# leak.net
KiCad netlist of a schematic drawn in EAGLE
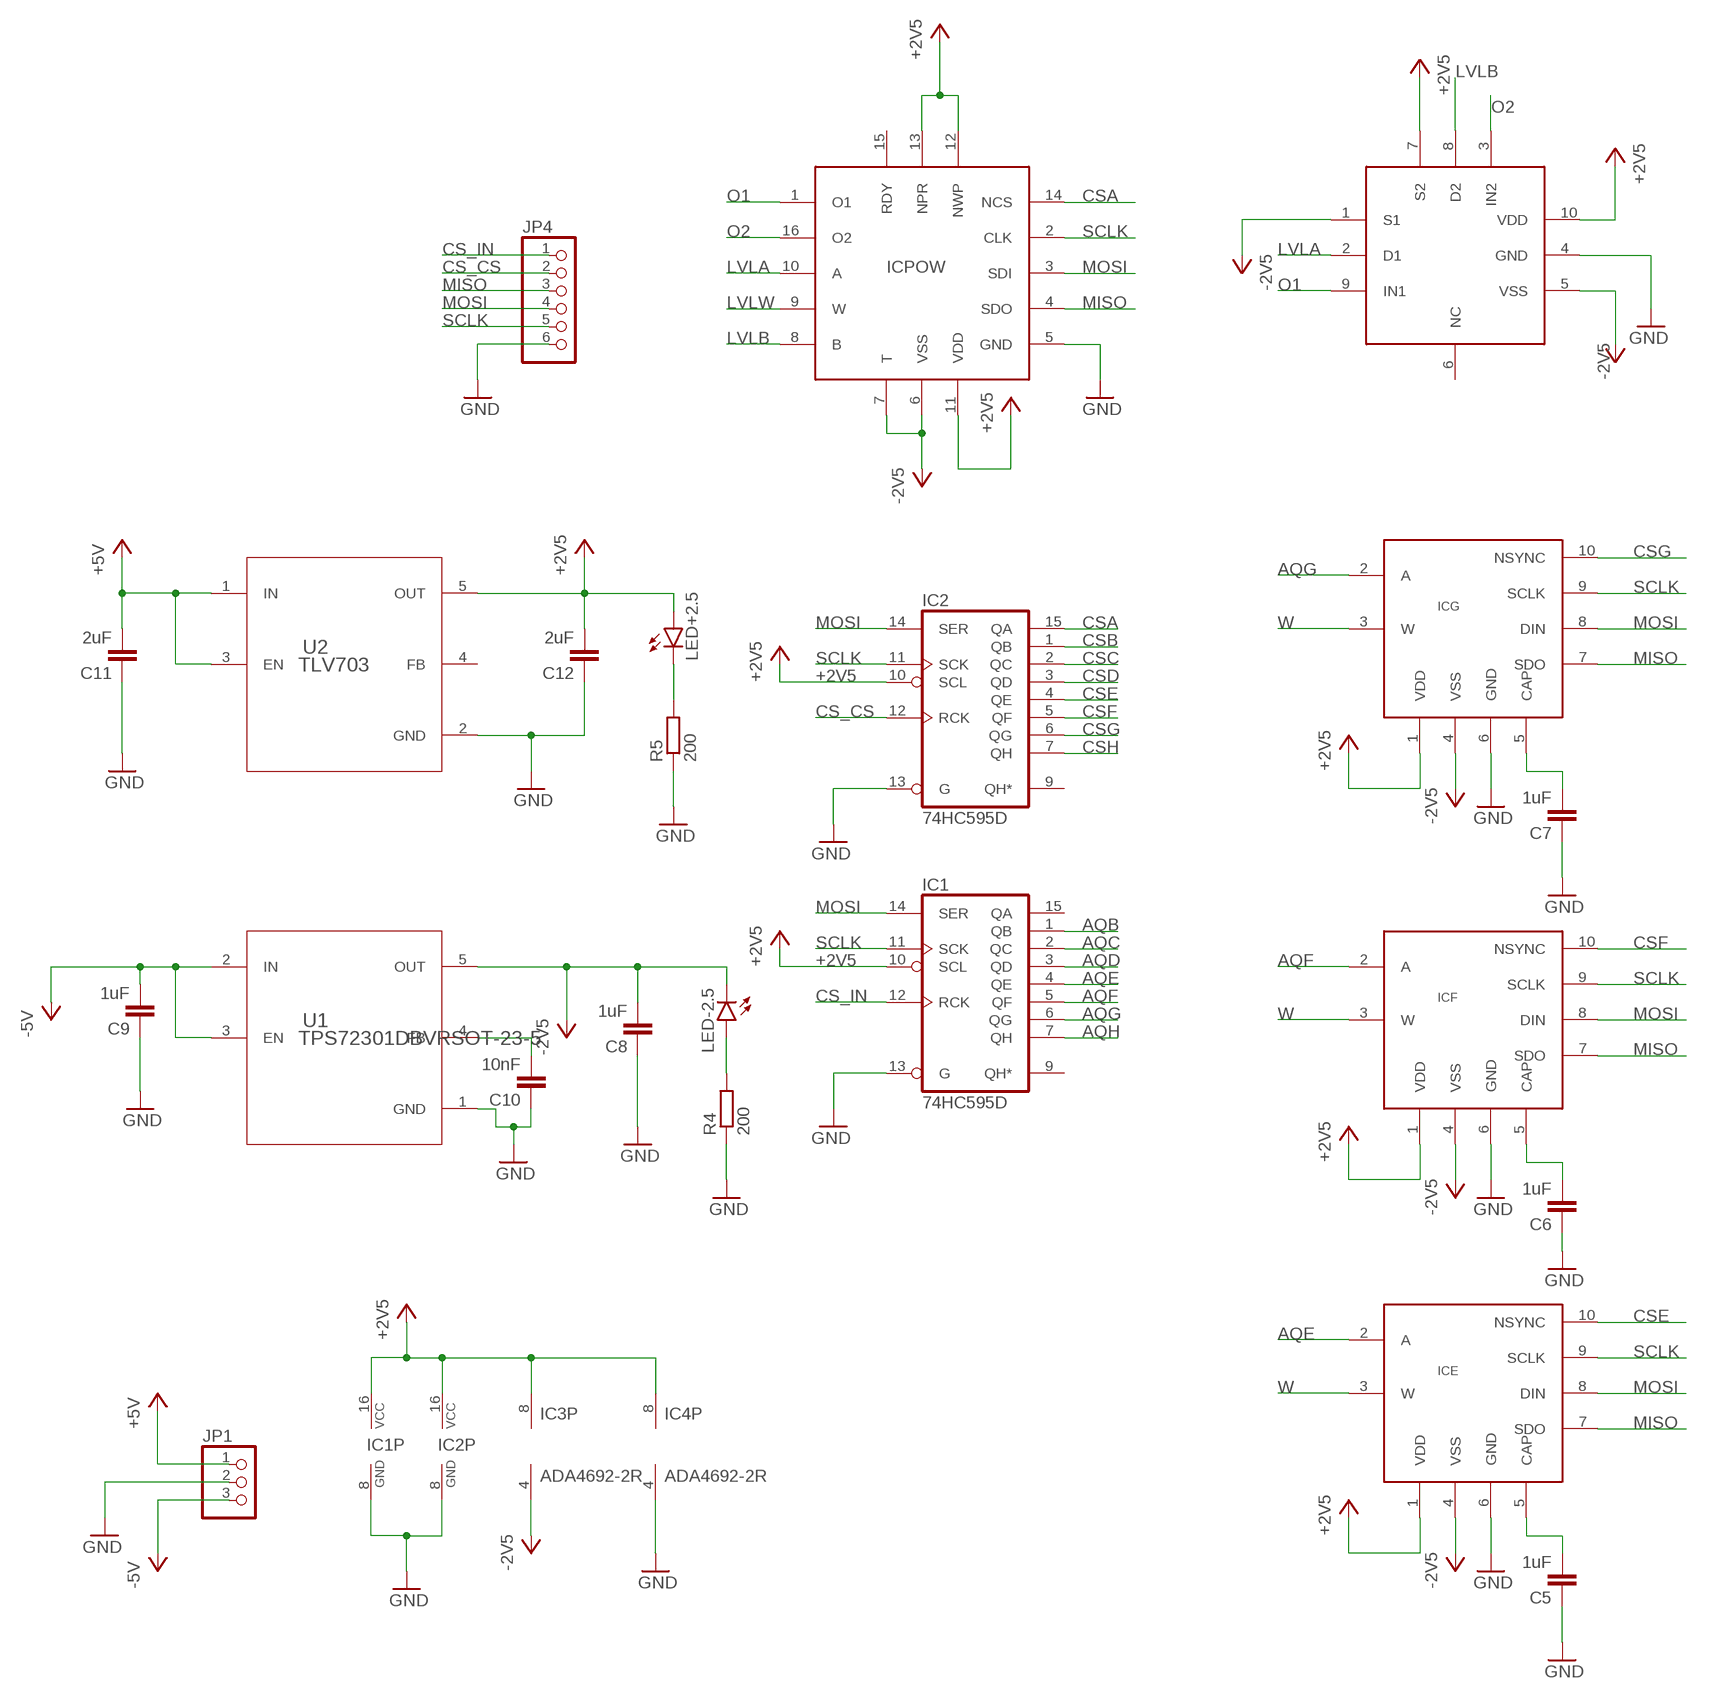
[diagram p0: schematic, sheet 1, part 1 of 2]
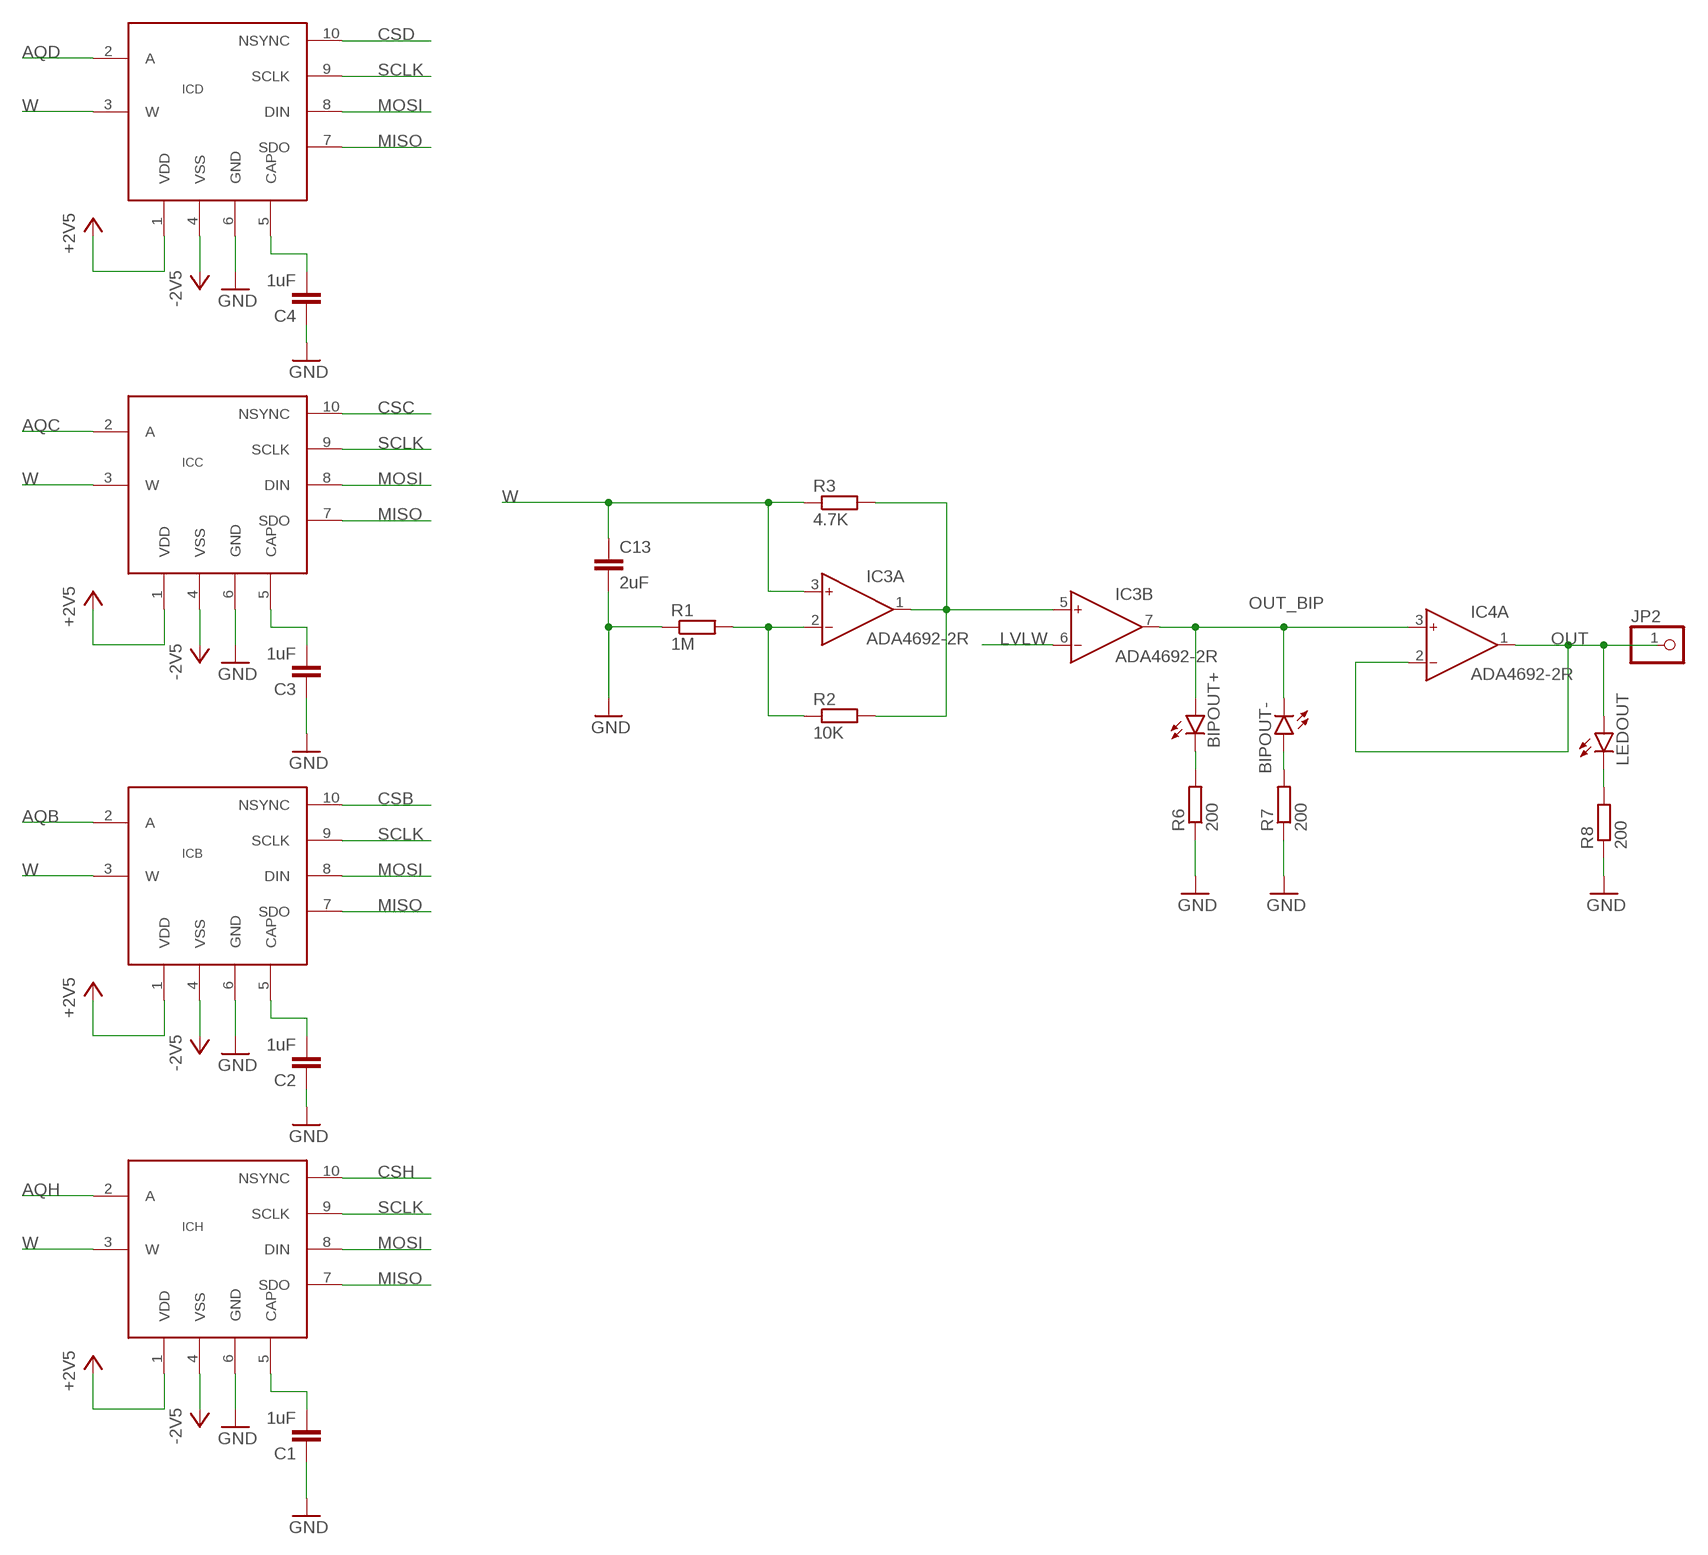
[diagram p1: schematic, sheet 1, part 2 of 2]

(export (version "E")
  (design (tool "Eeschema 10.0.6"))
  (components
    (comp (ref "BIPOUT+")
      (value "LEDCHIPLED_0805")
      (footprint "eagle-import:CHIPLED_0805")
      (libsource (lib "eagle-import") (part "LEDCHIPLED_0805"))
    )
    (comp (ref "BIPOUT-")
      (value "LEDCHIPLED_0805")
      (footprint "eagle-import:CHIPLED_0805")
      (libsource (lib "eagle-import") (part "LEDCHIPLED_0805"))
    )
    (comp (ref "C1")
      (value "1uF")
      (footprint "eagle-import:C0603")
      (libsource (lib "eagle-import") (part "C-EUC0603"))
    )
    (comp (ref "C2")
      (value "1uF")
      (footprint "eagle-import:C0603")
      (libsource (lib "eagle-import") (part "C-EUC0603"))
    )
    (comp (ref "C3")
      (value "1uF")
      (footprint "eagle-import:C0603")
      (libsource (lib "eagle-import") (part "C-EUC0603"))
    )
    (comp (ref "C4")
      (value "1uF")
      (footprint "eagle-import:C0603")
      (libsource (lib "eagle-import") (part "C-EUC0603"))
    )
    (comp (ref "C5")
      (value "1uF")
      (footprint "eagle-import:C0603")
      (libsource (lib "eagle-import") (part "C-EUC0603"))
    )
    (comp (ref "C6")
      (value "1uF")
      (footprint "eagle-import:C0603")
      (libsource (lib "eagle-import") (part "C-EUC0603"))
    )
    (comp (ref "C7")
      (value "1uF")
      (footprint "eagle-import:C0603")
      (libsource (lib "eagle-import") (part "C-EUC0603"))
    )
    (comp (ref "C8")
      (value "1uF")
      (footprint "eagle-import:C0603")
      (libsource (lib "eagle-import") (part "C-EUC0603"))
    )
    (comp (ref "C9")
      (value "1uF")
      (footprint "eagle-import:C0603")
      (libsource (lib "eagle-import") (part "C-EUC0603"))
    )
    (comp (ref "C10")
      (value "10nF")
      (footprint "eagle-import:C0603")
      (libsource (lib "eagle-import") (part "C-EUC0603"))
    )
    (comp (ref "C11")
      (value "2uF")
      (footprint "eagle-import:C0603")
      (libsource (lib "eagle-import") (part "C-EUC0603"))
    )
    (comp (ref "C12")
      (value "2uF")
      (footprint "eagle-import:C0603")
      (libsource (lib "eagle-import") (part "C-EUC0603"))
    )
    (comp (ref "C13")
      (value "2uF")
      (footprint "eagle-import:C0805K")
      (libsource (lib "eagle-import") (part "C-EUC0805K"))
    )
    (comp (ref "IC1")
      (value "74HC595D")
      (footprint "eagle-import:SO16")
      (libsource (lib "eagle-import") (part "74595DHC"))
    )
    (comp (ref "IC2")
      (value "74HC595D")
      (footprint "eagle-import:SO16")
      (libsource (lib "eagle-import") (part "74595DHC"))
    )
    (comp (ref "IC3")
      (value "ADA4692-2R")
      (footprint "eagle-import:SO8")
      (fields (field (name "MPN") "ADA4692-2ARZ"))
      (libsource (lib "eagle-import") (part "ADA4692-2R"))
    )
    (comp (ref "IC4")
      (value "ADA4692-2R")
      (footprint "eagle-import:SO8")
      (fields (field (name "MPN") "ADA4692-2ARZ"))
      (libsource (lib "eagle-import") (part "ADA4692-2R"))
    )
    (comp (ref "ICB")
      (value "AD5270MSOP10")
      (footprint "eagle-import:MSOP10")
      (libsource (lib "eagle-import") (part "AD5270MSOP10"))
    )
    (comp (ref "ICC")
      (value "AD5270MSOP10")
      (footprint "eagle-import:MSOP10")
      (libsource (lib "eagle-import") (part "AD5270MSOP10"))
    )
    (comp (ref "ICD")
      (value "AD5270MSOP10")
      (footprint "eagle-import:MSOP10")
      (libsource (lib "eagle-import") (part "AD5270MSOP10"))
    )
    (comp (ref "ICE")
      (value "AD5270MSOP10")
      (footprint "eagle-import:MSOP10")
      (libsource (lib "eagle-import") (part "AD5270MSOP10"))
    )
    (comp (ref "ICF")
      (value "AD5270MSOP10")
      (footprint "eagle-import:MSOP10")
      (libsource (lib "eagle-import") (part "AD5270MSOP10"))
    )
    (comp (ref "ICG")
      (value "AD5270MSOP10")
      (footprint "eagle-import:MSOP10")
      (libsource (lib "eagle-import") (part "AD5270MSOP10"))
    )
    (comp (ref "ICH")
      (value "AD5270MSOP10")
      (footprint "eagle-import:MSOP10")
      (libsource (lib "eagle-import") (part "AD5270MSOP10"))
    )
    (comp (ref "ICPOW")
      (value "AD5231")
      (footprint "eagle-import:TSSOP16")
      (libsource (lib "eagle-import") (part "AD5231"))
    )
    (comp (ref "ICSW")
      (value "ADG621")
      (footprint "eagle-import:MSOP10")
      (libsource (lib "eagle-import") (part "ADG621"))
    )
    (comp (ref "JP1")
      (value "PINHD-1X3")
      (footprint "eagle-import:1X03")
      (libsource (lib "eagle-import") (part "PINHD-1X3"))
    )
    (comp (ref "JP2")
      (value "PINHD-1X1")
      (footprint "eagle-import:1X01")
      (libsource (lib "eagle-import") (part "PINHD-1X1"))
    )
    (comp (ref "JP4")
      (value "PINHD-1X6")
      (footprint "eagle-import:1X06")
      (libsource (lib "eagle-import") (part "PINHD-1X6"))
    )
    (comp (ref "LED+2.5")
      (value "LEDCHIPLED_0805")
      (footprint "eagle-import:CHIPLED_0805")
      (libsource (lib "eagle-import") (part "LEDCHIPLED_0805"))
    )
    (comp (ref "LED-2.5")
      (value "LEDCHIPLED_0805")
      (footprint "eagle-import:CHIPLED_0805")
      (libsource (lib "eagle-import") (part "LEDCHIPLED_0805"))
    )
    (comp (ref "LEDOUT")
      (value "LEDCHIPLED_0805")
      (footprint "eagle-import:CHIPLED_0805")
      (libsource (lib "eagle-import") (part "LEDCHIPLED_0805"))
    )
    (comp (ref "R1")
      (value "1M")
      (footprint "eagle-import:R0805")
      (libsource (lib "eagle-import") (part "R-EU_R0805"))
    )
    (comp (ref "R2")
      (value "10K")
      (footprint "eagle-import:R0805")
      (libsource (lib "eagle-import") (part "R-EU_R0805"))
    )
    (comp (ref "R3")
      (value "4.7K")
      (footprint "eagle-import:R0805")
      (libsource (lib "eagle-import") (part "R-EU_R0805"))
    )
    (comp (ref "R4")
      (value "200")
      (footprint "eagle-import:R0603")
      (libsource (lib "eagle-import") (part "R-EU_R0603"))
    )
    (comp (ref "R5")
      (value "200")
      (footprint "eagle-import:R0603")
      (libsource (lib "eagle-import") (part "R-EU_R0603"))
    )
    (comp (ref "R6")
      (value "200")
      (footprint "eagle-import:R0603")
      (libsource (lib "eagle-import") (part "R-EU_R0603"))
    )
    (comp (ref "R7")
      (value "200")
      (footprint "eagle-import:R0603")
      (libsource (lib "eagle-import") (part "R-EU_R0603"))
    )
    (comp (ref "R8")
      (value "200")
      (footprint "eagle-import:R0603")
      (libsource (lib "eagle-import") (part "R-EU_R0603"))
    )
    (comp (ref "U1")
      (value "TPS72301DBVRSOT-23-5")
      (footprint "eagle-import:SOT95P280X145-5N")
      (libsource (lib "eagle-import") (part "TPS72301DBVRSOT-23-5"))
    )
    (comp (ref "U2")
      (value "TLV703")
      (footprint "eagle-import:SOT95P280X145-5N")
      (libsource (lib "eagle-import") (part "TLV703"))
    )
  )
  (nets
    (net (code "1") (name "+2V5") (class "Default")
      (node (ref "C12") (pin "2") (pinfunction "2_2") (pintype "passive"))
      (node (ref "IC1") (pin "10") (pinfunction "SCL_10") (pintype "input"))
      (node (ref "IC1") (pin "16") (pinfunction "VCC_16") (pintype "power_in"))
      (node (ref "IC2") (pin "10") (pinfunction "SCL_10") (pintype "input"))
      (node (ref "IC2") (pin "16") (pinfunction "VCC_16") (pintype "power_in"))
      (node (ref "IC3") (pin "8") (pinfunction "V+_8") (pintype "power_in"))
      (node (ref "IC4") (pin "8") (pinfunction "V+_8") (pintype "power_in"))
      (node (ref "ICB") (pin "1") (pinfunction "VDD_1") (pintype "bidirectional"))
      (node (ref "ICC") (pin "1") (pinfunction "VDD_1") (pintype "bidirectional"))
      (node (ref "ICD") (pin "1") (pinfunction "VDD_1") (pintype "bidirectional"))
      (node (ref "ICE") (pin "1") (pinfunction "VDD_1") (pintype "bidirectional"))
      (node (ref "ICF") (pin "1") (pinfunction "VDD_1") (pintype "bidirectional"))
      (node (ref "ICG") (pin "1") (pinfunction "VDD_1") (pintype "bidirectional"))
      (node (ref "ICH") (pin "1") (pinfunction "VDD_1") (pintype "bidirectional"))
      (node (ref "ICPOW") (pin "11") (pinfunction "VDD_11") (pintype "bidirectional"))
      (node (ref "ICPOW") (pin "12") (pinfunction "NWP_12") (pintype "bidirectional"))
      (node (ref "ICPOW") (pin "13") (pinfunction "NPR_13") (pintype "bidirectional"))
      (node (ref "ICSW") (pin "10") (pinfunction "VDD_10") (pintype "bidirectional"))
      (node (ref "ICSW") (pin "7") (pinfunction "S2_7") (pintype "bidirectional"))
      (node (ref "LED+2.5") (pin "A") (pinfunction "A_A") (pintype "passive"))
      (node (ref "U2") (pin "5") (pinfunction "OUT_5") (pintype "power_in"))
    )
    (net (code "2") (name "+5V") (class "Default")
      (node (ref "C11") (pin "2") (pinfunction "2_2") (pintype "passive"))
      (node (ref "JP1") (pin "1") (pinfunction "1_1") (pintype "passive"))
      (node (ref "U2") (pin "1") (pinfunction "IN_1") (pintype "power_in"))
      (node (ref "U2") (pin "3") (pinfunction "EN_3") (pintype "input"))
    )
    (net (code "3") (name "-2V5") (class "Default")
      (node (ref "C8") (pin "2") (pinfunction "2_2") (pintype "passive"))
      (node (ref "IC3") (pin "4") (pinfunction "V-_4") (pintype "power_in"))
      (node (ref "ICB") (pin "4") (pinfunction "VSS_4") (pintype "bidirectional"))
      (node (ref "ICC") (pin "4") (pinfunction "VSS_4") (pintype "bidirectional"))
      (node (ref "ICD") (pin "4") (pinfunction "VSS_4") (pintype "bidirectional"))
      (node (ref "ICE") (pin "4") (pinfunction "VSS_4") (pintype "bidirectional"))
      (node (ref "ICF") (pin "4") (pinfunction "VSS_4") (pintype "bidirectional"))
      (node (ref "ICG") (pin "4") (pinfunction "VSS_4") (pintype "bidirectional"))
      (node (ref "ICH") (pin "4") (pinfunction "VSS_4") (pintype "bidirectional"))
      (node (ref "ICPOW") (pin "6") (pinfunction "VSS_6") (pintype "bidirectional"))
      (node (ref "ICPOW") (pin "7") (pinfunction "T_7") (pintype "bidirectional"))
      (node (ref "ICSW") (pin "1") (pinfunction "S1_1") (pintype "bidirectional"))
      (node (ref "ICSW") (pin "5") (pinfunction "VSS_5") (pintype "bidirectional"))
      (node (ref "LED-2.5") (pin "C") (pinfunction "C_C") (pintype "passive"))
      (node (ref "U1") (pin "5") (pinfunction "OUT_5") (pintype "power_in"))
    )
    (net (code "4") (name "-5V") (class "Default")
      (node (ref "C9") (pin "2") (pinfunction "2_2") (pintype "passive"))
      (node (ref "JP1") (pin "3") (pinfunction "3_3") (pintype "passive"))
      (node (ref "U1") (pin "2") (pinfunction "IN_2") (pintype "power_in"))
      (node (ref "U1") (pin "3") (pinfunction "EN_3") (pintype "input"))
    )
    (net (code "5") (name "/AQB") (class "Default")
      (node (ref "IC1") (pin "1") (pinfunction "QB_1") (pintype "tri_state"))
      (node (ref "ICB") (pin "2") (pinfunction "A_2") (pintype "bidirectional"))
    )
    (net (code "6") (name "/AQC") (class "Default")
      (node (ref "IC1") (pin "2") (pinfunction "QC_2") (pintype "tri_state"))
      (node (ref "ICC") (pin "2") (pinfunction "A_2") (pintype "bidirectional"))
    )
    (net (code "7") (name "/AQD") (class "Default")
      (node (ref "IC1") (pin "3") (pinfunction "QD_3") (pintype "tri_state"))
      (node (ref "ICD") (pin "2") (pinfunction "A_2") (pintype "bidirectional"))
    )
    (net (code "8") (name "/AQE") (class "Default")
      (node (ref "IC1") (pin "4") (pinfunction "QE_4") (pintype "tri_state"))
      (node (ref "ICE") (pin "2") (pinfunction "A_2") (pintype "bidirectional"))
    )
    (net (code "9") (name "/AQF") (class "Default")
      (node (ref "IC1") (pin "5") (pinfunction "QF_5") (pintype "tri_state"))
      (node (ref "ICF") (pin "2") (pinfunction "A_2") (pintype "bidirectional"))
    )
    (net (code "10") (name "/AQG") (class "Default")
      (node (ref "IC1") (pin "6") (pinfunction "QG_6") (pintype "tri_state"))
      (node (ref "ICG") (pin "2") (pinfunction "A_2") (pintype "bidirectional"))
    )
    (net (code "11") (name "/AQH") (class "Default")
      (node (ref "IC1") (pin "7") (pinfunction "QH_7") (pintype "tri_state"))
      (node (ref "ICH") (pin "2") (pinfunction "A_2") (pintype "bidirectional"))
    )
    (net (code "12") (name "/CSA") (class "Default")
      (node (ref "IC2") (pin "15") (pinfunction "QA_15") (pintype "tri_state"))
      (node (ref "ICPOW") (pin "14") (pinfunction "NCS_14") (pintype "bidirectional"))
    )
    (net (code "13") (name "/CSB") (class "Default")
      (node (ref "IC2") (pin "1") (pinfunction "QB_1") (pintype "tri_state"))
      (node (ref "ICB") (pin "10") (pinfunction "NSYNC_10") (pintype "bidirectional"))
    )
    (net (code "14") (name "/CSC") (class "Default")
      (node (ref "IC2") (pin "2") (pinfunction "QC_2") (pintype "tri_state"))
      (node (ref "ICC") (pin "10") (pinfunction "NSYNC_10") (pintype "bidirectional"))
    )
    (net (code "15") (name "/CSD") (class "Default")
      (node (ref "IC2") (pin "3") (pinfunction "QD_3") (pintype "tri_state"))
      (node (ref "ICD") (pin "10") (pinfunction "NSYNC_10") (pintype "bidirectional"))
    )
    (net (code "16") (name "/CSE") (class "Default")
      (node (ref "IC2") (pin "4") (pinfunction "QE_4") (pintype "tri_state"))
      (node (ref "ICE") (pin "10") (pinfunction "NSYNC_10") (pintype "bidirectional"))
    )
    (net (code "17") (name "/CSF") (class "Default")
      (node (ref "IC2") (pin "5") (pinfunction "QF_5") (pintype "tri_state"))
      (node (ref "ICF") (pin "10") (pinfunction "NSYNC_10") (pintype "bidirectional"))
    )
    (net (code "18") (name "/CSG") (class "Default")
      (node (ref "IC2") (pin "6") (pinfunction "QG_6") (pintype "tri_state"))
      (node (ref "ICG") (pin "10") (pinfunction "NSYNC_10") (pintype "bidirectional"))
    )
    (net (code "19") (name "/CSH") (class "Default")
      (node (ref "IC2") (pin "7") (pinfunction "QH_7") (pintype "tri_state"))
      (node (ref "ICH") (pin "10") (pinfunction "NSYNC_10") (pintype "bidirectional"))
    )
    (net (code "20") (name "/CS_CS") (class "Default")
      (node (ref "IC2") (pin "12") (pinfunction "RCK_12") (pintype "input"))
      (node (ref "JP4") (pin "2") (pinfunction "2_2") (pintype "passive"))
    )
    (net (code "21") (name "/CS_IN") (class "Default")
      (node (ref "IC1") (pin "12") (pinfunction "RCK_12") (pintype "input"))
      (node (ref "JP4") (pin "1") (pinfunction "1_1") (pintype "passive"))
    )
    (net (code "22") (name "/LVLA") (class "Default")
      (node (ref "ICPOW") (pin "10") (pinfunction "A_10") (pintype "bidirectional"))
      (node (ref "ICSW") (pin "2") (pinfunction "D1_2") (pintype "bidirectional"))
    )
    (net (code "23") (name "/LVLB") (class "Default")
      (node (ref "ICPOW") (pin "8") (pinfunction "B_8") (pintype "bidirectional"))
      (node (ref "ICSW") (pin "8") (pinfunction "D2_8") (pintype "bidirectional"))
    )
    (net (code "24") (name "/LVLW") (class "Default")
      (node (ref "IC3") (pin "6") (pinfunction "IN-_6") (pintype "input"))
      (node (ref "ICPOW") (pin "9") (pinfunction "W_9") (pintype "bidirectional"))
    )
    (net (code "25") (name "/MISO") (class "Default")
      (node (ref "ICB") (pin "7") (pinfunction "SDO_7") (pintype "bidirectional"))
      (node (ref "ICC") (pin "7") (pinfunction "SDO_7") (pintype "bidirectional"))
      (node (ref "ICD") (pin "7") (pinfunction "SDO_7") (pintype "bidirectional"))
      (node (ref "ICE") (pin "7") (pinfunction "SDO_7") (pintype "bidirectional"))
      (node (ref "ICF") (pin "7") (pinfunction "SDO_7") (pintype "bidirectional"))
      (node (ref "ICG") (pin "7") (pinfunction "SDO_7") (pintype "bidirectional"))
      (node (ref "ICH") (pin "7") (pinfunction "SDO_7") (pintype "bidirectional"))
      (node (ref "ICPOW") (pin "4") (pinfunction "SDO_4") (pintype "bidirectional"))
      (node (ref "JP4") (pin "3") (pinfunction "3_3") (pintype "passive"))
    )
    (net (code "26") (name "/MOSI") (class "Default")
      (node (ref "IC1") (pin "14") (pinfunction "SER_14") (pintype "input"))
      (node (ref "IC2") (pin "14") (pinfunction "SER_14") (pintype "input"))
      (node (ref "ICB") (pin "8") (pinfunction "DIN_8") (pintype "bidirectional"))
      (node (ref "ICC") (pin "8") (pinfunction "DIN_8") (pintype "bidirectional"))
      (node (ref "ICD") (pin "8") (pinfunction "DIN_8") (pintype "bidirectional"))
      (node (ref "ICE") (pin "8") (pinfunction "DIN_8") (pintype "bidirectional"))
      (node (ref "ICF") (pin "8") (pinfunction "DIN_8") (pintype "bidirectional"))
      (node (ref "ICG") (pin "8") (pinfunction "DIN_8") (pintype "bidirectional"))
      (node (ref "ICH") (pin "8") (pinfunction "DIN_8") (pintype "bidirectional"))
      (node (ref "ICPOW") (pin "3") (pinfunction "SDI_3") (pintype "bidirectional"))
      (node (ref "JP4") (pin "4") (pinfunction "4_4") (pintype "passive"))
    )
    (net (code "27") (name "/O1") (class "Default")
      (node (ref "ICPOW") (pin "1") (pinfunction "O1_1") (pintype "bidirectional"))
      (node (ref "ICSW") (pin "9") (pinfunction "IN1_9") (pintype "bidirectional"))
    )
    (net (code "28") (name "/O2") (class "Default")
      (node (ref "ICPOW") (pin "16") (pinfunction "O2_16") (pintype "bidirectional"))
      (node (ref "ICSW") (pin "3") (pinfunction "IN2_3") (pintype "bidirectional"))
    )
    (net (code "29") (name "/OUT") (class "Default")
      (node (ref "IC4") (pin "1") (pinfunction "OUT_1") (pintype "output"))
      (node (ref "IC4") (pin "2") (pinfunction "IN-_2") (pintype "input"))
      (node (ref "JP2") (pin "1") (pinfunction "1_1") (pintype "passive"))
      (node (ref "LEDOUT") (pin "A") (pinfunction "A_A") (pintype "passive"))
    )
    (net (code "30") (name "/OUT_BIP") (class "Default")
      (node (ref "BIPOUT+") (pin "A") (pinfunction "A_A") (pintype "passive"))
      (node (ref "BIPOUT-") (pin "C") (pinfunction "C_C") (pintype "passive"))
      (node (ref "IC3") (pin "7") (pinfunction "OUT_7") (pintype "output"))
      (node (ref "IC4") (pin "3") (pinfunction "IN+_3") (pintype "input"))
    )
    (net (code "31") (name "/SCLK") (class "Default")
      (node (ref "IC1") (pin "11") (pinfunction "SCK_11") (pintype "input"))
      (node (ref "IC2") (pin "11") (pinfunction "SCK_11") (pintype "input"))
      (node (ref "ICB") (pin "9") (pinfunction "SCLK_9") (pintype "bidirectional"))
      (node (ref "ICC") (pin "9") (pinfunction "SCLK_9") (pintype "bidirectional"))
      (node (ref "ICD") (pin "9") (pinfunction "SCLK_9") (pintype "bidirectional"))
      (node (ref "ICE") (pin "9") (pinfunction "SCLK_9") (pintype "bidirectional"))
      (node (ref "ICF") (pin "9") (pinfunction "SCLK_9") (pintype "bidirectional"))
      (node (ref "ICG") (pin "9") (pinfunction "SCLK_9") (pintype "bidirectional"))
      (node (ref "ICH") (pin "9") (pinfunction "SCLK_9") (pintype "bidirectional"))
      (node (ref "ICPOW") (pin "2") (pinfunction "CLK_2") (pintype "bidirectional"))
      (node (ref "JP4") (pin "5") (pinfunction "5_5") (pintype "passive"))
    )
    (net (code "32") (name "/W") (class "Default")
      (node (ref "C13") (pin "1") (pinfunction "1_1") (pintype "passive"))
      (node (ref "IC3") (pin "3") (pinfunction "IN+_3") (pintype "input"))
      (node (ref "ICB") (pin "3") (pinfunction "W_3") (pintype "bidirectional"))
      (node (ref "ICC") (pin "3") (pinfunction "W_3") (pintype "bidirectional"))
      (node (ref "ICD") (pin "3") (pinfunction "W_3") (pintype "bidirectional"))
      (node (ref "ICE") (pin "3") (pinfunction "W_3") (pintype "bidirectional"))
      (node (ref "ICF") (pin "3") (pinfunction "W_3") (pintype "bidirectional"))
      (node (ref "ICG") (pin "3") (pinfunction "W_3") (pintype "bidirectional"))
      (node (ref "ICH") (pin "3") (pinfunction "W_3") (pintype "bidirectional"))
      (node (ref "R3") (pin "1") (pinfunction "1_1") (pintype "passive"))
    )
    (net (code "33") (name "GND") (class "Default")
      (node (ref "C1") (pin "1") (pinfunction "1_1") (pintype "passive"))
      (node (ref "C10") (pin "1") (pinfunction "1_1") (pintype "passive"))
      (node (ref "C11") (pin "1") (pinfunction "1_1") (pintype "passive"))
      (node (ref "C12") (pin "1") (pinfunction "1_1") (pintype "passive"))
      (node (ref "C13") (pin "2") (pinfunction "2_2") (pintype "passive"))
      (node (ref "C2") (pin "1") (pinfunction "1_1") (pintype "passive"))
      (node (ref "C3") (pin "1") (pinfunction "1_1") (pintype "passive"))
      (node (ref "C4") (pin "1") (pinfunction "1_1") (pintype "passive"))
      (node (ref "C5") (pin "1") (pinfunction "1_1") (pintype "passive"))
      (node (ref "C6") (pin "1") (pinfunction "1_1") (pintype "passive"))
      (node (ref "C7") (pin "1") (pinfunction "1_1") (pintype "passive"))
      (node (ref "C8") (pin "1") (pinfunction "1_1") (pintype "passive"))
      (node (ref "C9") (pin "1") (pinfunction "1_1") (pintype "passive"))
      (node (ref "IC1") (pin "13") (pinfunction "G_13") (pintype "input"))
      (node (ref "IC1") (pin "8") (pinfunction "GND_8") (pintype "power_in"))
      (node (ref "IC2") (pin "13") (pinfunction "G_13") (pintype "input"))
      (node (ref "IC2") (pin "8") (pinfunction "GND_8") (pintype "power_in"))
      (node (ref "IC4") (pin "4") (pinfunction "V-_4") (pintype "power_in"))
      (node (ref "ICB") (pin "6") (pinfunction "GND_6") (pintype "bidirectional"))
      (node (ref "ICC") (pin "6") (pinfunction "GND_6") (pintype "bidirectional"))
      (node (ref "ICD") (pin "6") (pinfunction "GND_6") (pintype "bidirectional"))
      (node (ref "ICE") (pin "6") (pinfunction "GND_6") (pintype "bidirectional"))
      (node (ref "ICF") (pin "6") (pinfunction "GND_6") (pintype "bidirectional"))
      (node (ref "ICG") (pin "6") (pinfunction "GND_6") (pintype "bidirectional"))
      (node (ref "ICH") (pin "6") (pinfunction "GND_6") (pintype "bidirectional"))
      (node (ref "ICPOW") (pin "5") (pinfunction "GND_5") (pintype "bidirectional"))
      (node (ref "ICSW") (pin "4") (pinfunction "GND_4") (pintype "bidirectional"))
      (node (ref "JP1") (pin "2") (pinfunction "2_2") (pintype "passive"))
      (node (ref "JP4") (pin "6") (pinfunction "6_6") (pintype "passive"))
      (node (ref "R1") (pin "1") (pinfunction "1_1") (pintype "passive"))
      (node (ref "R4") (pin "1") (pinfunction "1_1") (pintype "passive"))
      (node (ref "R5") (pin "1") (pinfunction "1_1") (pintype "passive"))
      (node (ref "R6") (pin "1") (pinfunction "1_1") (pintype "passive"))
      (node (ref "R7") (pin "1") (pinfunction "1_1") (pintype "passive"))
      (node (ref "R8") (pin "1") (pinfunction "1_1") (pintype "passive"))
      (node (ref "U1") (pin "1") (pinfunction "GND_1") (pintype "power_in"))
      (node (ref "U2") (pin "2") (pinfunction "GND_2") (pintype "power_in"))
    )
    (net (code "34") (name "Net-(BIPOUT+-PadC)") (class "Default")
      (node (ref "BIPOUT+") (pin "C") (pinfunction "C_C") (pintype "passive"))
      (node (ref "R6") (pin "2") (pinfunction "2_2") (pintype "passive"))
    )
    (net (code "35") (name "Net-(BIPOUT--PadA)") (class "Default")
      (node (ref "BIPOUT-") (pin "A") (pinfunction "A_A") (pintype "passive"))
      (node (ref "R7") (pin "2") (pinfunction "2_2") (pintype "passive"))
    )
    (net (code "36") (name "Net-(IC3A-IN-)") (class "Default")
      (node (ref "IC3") (pin "2") (pinfunction "IN-_2") (pintype "input"))
      (node (ref "R1") (pin "2") (pinfunction "2_2") (pintype "passive"))
      (node (ref "R2") (pin "1") (pinfunction "1_1") (pintype "passive"))
    )
    (net (code "37") (name "Net-(IC3A-OUT)") (class "Default")
      (node (ref "IC3") (pin "1") (pinfunction "OUT_1") (pintype "output"))
      (node (ref "IC3") (pin "5") (pinfunction "IN+_5") (pintype "input"))
      (node (ref "R2") (pin "2") (pinfunction "2_2") (pintype "passive"))
      (node (ref "R3") (pin "2") (pinfunction "2_2") (pintype "passive"))
    )
    (net (code "38") (name "Net-(ICB-CAP)") (class "Default")
      (node (ref "C2") (pin "2") (pinfunction "2_2") (pintype "passive"))
      (node (ref "ICB") (pin "5") (pinfunction "CAP_5") (pintype "bidirectional"))
    )
    (net (code "39") (name "Net-(ICC-CAP)") (class "Default")
      (node (ref "C3") (pin "2") (pinfunction "2_2") (pintype "passive"))
      (node (ref "ICC") (pin "5") (pinfunction "CAP_5") (pintype "bidirectional"))
    )
    (net (code "40") (name "Net-(ICD-CAP)") (class "Default")
      (node (ref "C4") (pin "2") (pinfunction "2_2") (pintype "passive"))
      (node (ref "ICD") (pin "5") (pinfunction "CAP_5") (pintype "bidirectional"))
    )
    (net (code "41") (name "Net-(ICE-CAP)") (class "Default")
      (node (ref "C5") (pin "2") (pinfunction "2_2") (pintype "passive"))
      (node (ref "ICE") (pin "5") (pinfunction "CAP_5") (pintype "bidirectional"))
    )
    (net (code "42") (name "Net-(ICF-CAP)") (class "Default")
      (node (ref "C6") (pin "2") (pinfunction "2_2") (pintype "passive"))
      (node (ref "ICF") (pin "5") (pinfunction "CAP_5") (pintype "bidirectional"))
    )
    (net (code "43") (name "Net-(ICG-CAP)") (class "Default")
      (node (ref "C7") (pin "2") (pinfunction "2_2") (pintype "passive"))
      (node (ref "ICG") (pin "5") (pinfunction "CAP_5") (pintype "bidirectional"))
    )
    (net (code "44") (name "Net-(ICH-CAP)") (class "Default")
      (node (ref "C1") (pin "2") (pinfunction "2_2") (pintype "passive"))
      (node (ref "ICH") (pin "5") (pinfunction "CAP_5") (pintype "bidirectional"))
    )
    (net (code "45") (name "Net-(LED+2.5-PadC)") (class "Default")
      (node (ref "LED+2.5") (pin "C") (pinfunction "C_C") (pintype "passive"))
      (node (ref "R5") (pin "2") (pinfunction "2_2") (pintype "passive"))
    )
    (net (code "46") (name "Net-(LED-2.5-PadA)") (class "Default")
      (node (ref "LED-2.5") (pin "A") (pinfunction "A_A") (pintype "passive"))
      (node (ref "R4") (pin "2") (pinfunction "2_2") (pintype "passive"))
    )
    (net (code "47") (name "Net-(LEDOUT-PadC)") (class "Default")
      (node (ref "LEDOUT") (pin "C") (pinfunction "C_C") (pintype "passive"))
      (node (ref "R8") (pin "2") (pinfunction "2_2") (pintype "passive"))
    )
    (net (code "48") (name "Net-(U1-FB)") (class "Default")
      (node (ref "C10") (pin "2") (pinfunction "2_2") (pintype "passive"))
      (node (ref "U1") (pin "4") (pinfunction "FB_4") (pintype "input"))
    )
    (net (code "49") (name "unconnected-(IC1A-QA-Pad15)") (class "Default")
      (node (ref "IC1") (pin "15") (pinfunction "QA_15") (pintype "tri_state"))
    )
    (net (code "50") (name "unconnected-(IC1A-QH*-Pad9)") (class "Default")
      (node (ref "IC1") (pin "9") (pinfunction "QH*_9") (pintype "tri_state"))
    )
    (net (code "51") (name "unconnected-(IC2A-QH*-Pad9)") (class "Default")
      (node (ref "IC2") (pin "9") (pinfunction "QH*_9") (pintype "tri_state"))
    )
    (net (code "52") (name "unconnected-(ICPOW-RDY-Pad15)") (class "Default")
      (node (ref "ICPOW") (pin "15") (pinfunction "RDY_15") (pintype "bidirectional"))
    )
    (net (code "53") (name "unconnected-(ICSW-NC-Pad6)") (class "Default")
      (node (ref "ICSW") (pin "6") (pinfunction "NC_6") (pintype "bidirectional"))
    )
    (net (code "54") (name "unconnected-(U2-FB-Pad4)") (class "Default")
      (node (ref "U2") (pin "4") (pinfunction "FB_4") (pintype "input"))
    )
  )
)
